# Relay_Switch.net
KiCad netlist of a schematic drawn in EAGLE
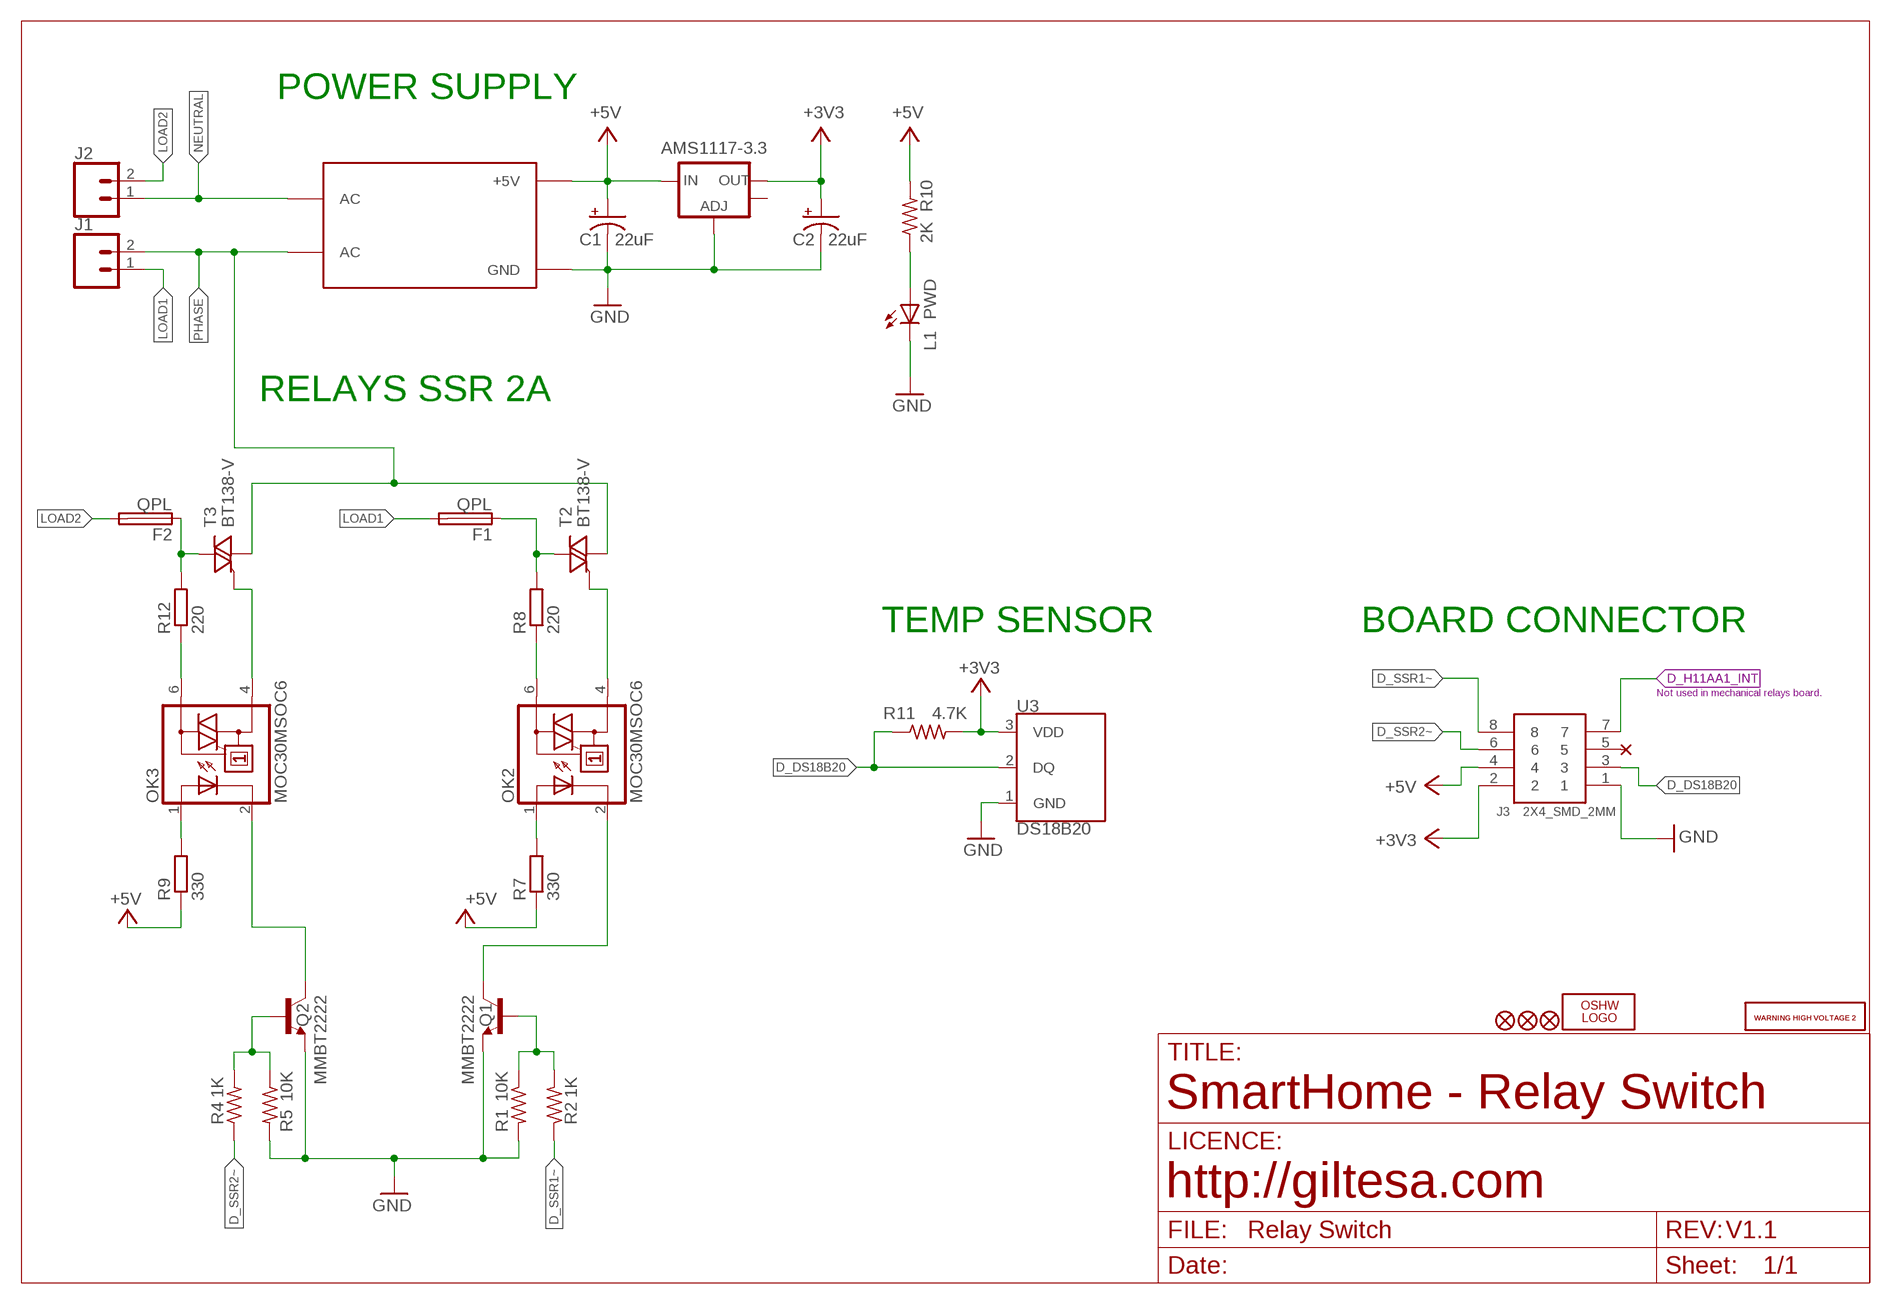
[diagram p0: schematic, sheet 1]

(export (version "E")
  (design (tool "Eeschema 10.0.6"))
  (components
    (comp (ref "AMS1117-3.3")
      (value "V_REG_LM1117SOT223")
      (footprint "eagle-import:SOT223")
      (libsource (lib "eagle-import") (part "V_REG_LM1117SOT223"))
    )
    (comp (ref "C1")
      (value "22uF")
      (footprint "eagle-import:EIA3528")
      (libsource (lib "eagle-import") (part "CAP_POL3528"))
    )
    (comp (ref "C2")
      (value "22uF")
      (footprint "eagle-import:EIA3528")
      (libsource (lib "eagle-import") (part "CAP_POL3528"))
    )
    (comp (ref "F1")
      (value "QPL")
      (footprint "eagle-import:TE5")
      (libsource (lib "eagle-import") (part "TE5"))
    )
    (comp (ref "F2")
      (value "QPL")
      (footprint "eagle-import:TE5")
      (libsource (lib "eagle-import") (part "TE5"))
    )
    (comp (ref "J1")
      (value "TERMINAL_5MM_2P")
      (footprint "eagle-import:TERMINAL_5MM_2P")
      (libsource (lib "eagle-import") (part "TERMINAL_5MM_2P"))
    )
    (comp (ref "J2")
      (value "TERMINAL_5MM_2P")
      (footprint "eagle-import:TERMINAL_5MM_2P")
      (libsource (lib "eagle-import") (part "TERMINAL_5MM_2P"))
    )
    (comp (ref "J3")
      (value "2X4_SMD_2MM")
      (footprint "eagle-import:2X4_SMD_2.0MM")
      (libsource (lib "eagle-import") (part "2X4_SMD_2.0MM"))
    )
    (comp (ref "L1")
      (value "PWD")
      (footprint "eagle-import:CHIP-LED0805")
      (libsource (lib "eagle-import") (part "LEDCHIP-LED0805"))
    )
    (comp (ref "LOGO1")
      (value "OSHW_LOGO_FILLX0150-NT")
      (footprint "eagle-import:OSHW_FILLX150_NOTEXT")
      (libsource (lib "eagle-import") (part "OSHW_LOGO_FILLX0150-NT"))
    )
    (comp (ref "OK2")
      (value "MOC30MSOC6")
      (footprint "eagle-import:DIL6-SMD")
      (libsource (lib "eagle-import") (part "MOC30MSOC6"))
    )
    (comp (ref "OK3")
      (value "MOC30MSOC6")
      (footprint "eagle-import:DIL6-SMD")
      (libsource (lib "eagle-import") (part "MOC30MSOC6"))
    )
    (comp (ref "Q1")
      (value "MMBT2222")
      (footprint "eagle-import:SOT23")
      (libsource (lib "eagle-import") (part "TRANSISTOR_NPNSOT23"))
    )
    (comp (ref "Q2")
      (value "MMBT2222")
      (footprint "eagle-import:SOT23")
      (libsource (lib "eagle-import") (part "TRANSISTOR_NPNSOT23"))
    )
    (comp (ref "R1")
      (value "10K")
      (footprint "eagle-import:R0603")
      (libsource (lib "eagle-import") (part "R0603"))
    )
    (comp (ref "R2")
      (value "1K")
      (footprint "eagle-import:R0603")
      (libsource (lib "eagle-import") (part "R0603"))
    )
    (comp (ref "R4")
      (value "1K")
      (footprint "eagle-import:R0603")
      (libsource (lib "eagle-import") (part "R0603"))
    )
    (comp (ref "R5")
      (value "10K")
      (footprint "eagle-import:R0603")
      (libsource (lib "eagle-import") (part "R0603"))
    )
    (comp (ref "R7")
      (value "330")
      (footprint "eagle-import:M0805")
      (libsource (lib "eagle-import") (part "R-EU_M0805"))
    )
    (comp (ref "R8")
      (value "220")
      (footprint "eagle-import:M0805")
      (libsource (lib "eagle-import") (part "R-EU_M0805"))
    )
    (comp (ref "R9")
      (value "330")
      (footprint "eagle-import:M0805")
      (libsource (lib "eagle-import") (part "R-EU_M0805"))
    )
    (comp (ref "R10")
      (value "2K")
      (footprint "eagle-import:R0603")
      (libsource (lib "eagle-import") (part "R0603"))
    )
    (comp (ref "R11")
      (value "4.7K")
      (footprint "eagle-import:R0603")
      (libsource (lib "eagle-import") (part "R0603"))
    )
    (comp (ref "R12")
      (value "220")
      (footprint "eagle-import:M0805")
      (libsource (lib "eagle-import") (part "R-EU_M0805"))
    )
    (comp (ref "T2")
      (value "BT138-V")
      (footprint "eagle-import:TO220BV")
      (libsource (lib "eagle-import") (part "BT138-V"))
    )
    (comp (ref "T3")
      (value "BT138-V")
      (footprint "eagle-import:TO220BV")
      (libsource (lib "eagle-import") (part "BT138-V"))
    )
    (comp (ref "U$1")
      (value "HILINK_HLK-PM01_5V")
      (footprint "eagle-import:HILINK_HLK-PM01_5V")
      (libsource (lib "eagle-import") (part "HILINK_HLK-PM01_5V"))
    )
    (comp (ref "U$3")
      (value "WARNING_HIGH_VOLTAGE_2")
      (footprint "eagle-import:WARNING_HIGH_VOLTAGE_2")
      (libsource (lib "eagle-import") (part "WARNING_HIGH_VOLTAGE_2"))
    )
    (comp (ref "U$4")
      (value "WARNING_HIGH_VOLTAGE_2")
      (footprint "eagle-import:WARNING_HIGH_VOLTAGE_2")
      (libsource (lib "eagle-import") (part "WARNING_HIGH_VOLTAGE_2"))
    )
    (comp (ref "U$6")
      (value "FIDUCIAL1X2")
      (footprint "eagle-import:FIDUCIAL-1X2")
      (libsource (lib "eagle-import") (part "FIDUCIAL1X2"))
    )
    (comp (ref "U$7")
      (value "FIDUCIAL1X2")
      (footprint "eagle-import:FIDUCIAL-1X2")
      (libsource (lib "eagle-import") (part "FIDUCIAL1X2"))
    )
    (comp (ref "U$14")
      (value "FIDUCIAL1X2")
      (footprint "eagle-import:FIDUCIAL-1X2")
      (libsource (lib "eagle-import") (part "FIDUCIAL1X2"))
    )
    (comp (ref "U3")
      (value "DS18B20")
      (footprint "eagle-import:DS18B20")
      (libsource (lib "eagle-import") (part "DS18B20"))
    )
  )
  (nets
    (net (code "1") (name "+3V3") (class "Default")
      (node (ref "AMS1117-3.3") (pin "2") (pinfunction "OUT_2") (pintype "output"))
      (node (ref "C2") (pin "A") (pinfunction "+_A") (pintype "passive"))
      (node (ref "J3") (pin "2") (pinfunction "2_2") (pintype "bidirectional"))
      (node (ref "R11") (pin "2") (pinfunction "2_2") (pintype "passive"))
      (node (ref "U3") (pin "3") (pinfunction "VDD_3") (pintype "power_in"))
    )
    (net (code "2") (name "+5V") (class "Default")
      (node (ref "AMS1117-3.3") (pin "3") (pinfunction "IN_3") (pintype "input"))
      (node (ref "C1") (pin "A") (pinfunction "+_A") (pintype "passive"))
      (node (ref "J3") (pin "4") (pinfunction "4_4") (pintype "bidirectional"))
      (node (ref "R10") (pin "2") (pinfunction "2_2") (pintype "passive"))
      (node (ref "R7") (pin "1") (pinfunction "1_1") (pintype "passive"))
      (node (ref "R9") (pin "1") (pinfunction "1_1") (pintype "passive"))
      (node (ref "U$1") (pin "+5V") (pinfunction "+5V_+5V") (pintype "output"))
    )
    (net (code "3") (name "/D_SSR1~{}") (class "Default")
      (node (ref "J3") (pin "8") (pinfunction "8_8") (pintype "bidirectional"))
      (node (ref "R2") (pin "1") (pinfunction "1_1") (pintype "passive"))
    )
    (net (code "4") (name "/D_SSR2~{}") (class "Default")
      (node (ref "J3") (pin "6") (pinfunction "6_6") (pintype "bidirectional"))
      (node (ref "R4") (pin "1") (pinfunction "1_1") (pintype "passive"))
    )
    (net (code "5") (name "D_DS18B20") (class "Default")
      (node (ref "J3") (pin "3") (pinfunction "3_3") (pintype "bidirectional"))
      (node (ref "R11") (pin "1") (pinfunction "1_1") (pintype "passive"))
      (node (ref "U3") (pin "2") (pinfunction "DQ_2") (pintype "bidirectional"))
    )
    (net (code "6") (name "D_H11AA1_INT") (class "Default")
      (node (ref "J3") (pin "7") (pinfunction "7_7") (pintype "bidirectional"))
    )
    (net (code "7") (name "GND") (class "Default")
      (node (ref "AMS1117-3.3") (pin "1") (pinfunction "ADJ_1") (pintype "input"))
      (node (ref "C1") (pin "C") (pinfunction "-_C") (pintype "passive"))
      (node (ref "C2") (pin "C") (pinfunction "-_C") (pintype "passive"))
      (node (ref "J3") (pin "1") (pinfunction "1_1") (pintype "bidirectional"))
      (node (ref "L1") (pin "C") (pinfunction "C_C") (pintype "passive"))
      (node (ref "Q1") (pin "2") (pinfunction "E_2") (pintype "passive"))
      (node (ref "Q2") (pin "2") (pinfunction "E_2") (pintype "passive"))
      (node (ref "R1") (pin "2") (pinfunction "2_2") (pintype "passive"))
      (node (ref "R5") (pin "2") (pinfunction "2_2") (pintype "passive"))
      (node (ref "U$1") (pin "GND") (pinfunction "GND_GND") (pintype "output"))
      (node (ref "U3") (pin "1") (pinfunction "GND_1") (pintype "power_in"))
    )
    (net (code "8") (name "LOAD1") (class "Default")
      (node (ref "F1") (pin "2") (pinfunction "2_2") (pintype "passive"))
      (node (ref "J1") (pin "1") (pinfunction "1_1") (pintype "passive"))
    )
    (net (code "9") (name "LOAD2") (class "Default")
      (node (ref "F2") (pin "2") (pinfunction "2_2") (pintype "passive"))
      (node (ref "J2") (pin "2") (pinfunction "2_2") (pintype "passive"))
    )
    (net (code "10") (name "NEUTRAL") (class "Default")
      (node (ref "J2") (pin "1") (pinfunction "1_1") (pintype "passive"))
      (node (ref "U$1") (pin "AC@2") (pinfunction "AC_AC@2") (pintype "input"))
    )
    (net (code "11") (name "Net-(L1-PadA)") (class "Default")
      (node (ref "L1") (pin "A") (pinfunction "A_A") (pintype "passive"))
      (node (ref "R10") (pin "1") (pinfunction "1_1") (pintype "passive"))
    )
    (net (code "12") (name "Net-(OK2-A)") (class "Default")
      (node (ref "OK2") (pin "1") (pinfunction "A_1") (pintype "passive"))
      (node (ref "R7") (pin "2") (pinfunction "2_2") (pintype "passive"))
    )
    (net (code "13") (name "Net-(OK2-A1)") (class "Default")
      (node (ref "OK2") (pin "4") (pinfunction "A1_4") (pintype "passive"))
      (node (ref "T2") (pin "G") (pinfunction "G_G") (pintype "passive"))
    )
    (net (code "14") (name "Net-(OK2-A2)") (class "Default")
      (node (ref "OK2") (pin "6") (pinfunction "A2_6") (pintype "passive"))
      (node (ref "R8") (pin "1") (pinfunction "1_1") (pintype "passive"))
    )
    (net (code "15") (name "Net-(OK2-C)") (class "Default")
      (node (ref "OK2") (pin "2") (pinfunction "C_2") (pintype "passive"))
      (node (ref "Q1") (pin "3") (pinfunction "C_3") (pintype "passive"))
    )
    (net (code "16") (name "Net-(OK3-A)") (class "Default")
      (node (ref "OK3") (pin "1") (pinfunction "A_1") (pintype "passive"))
      (node (ref "R9") (pin "2") (pinfunction "2_2") (pintype "passive"))
    )
    (net (code "17") (name "Net-(OK3-A1)") (class "Default")
      (node (ref "OK3") (pin "4") (pinfunction "A1_4") (pintype "passive"))
      (node (ref "T3") (pin "G") (pinfunction "G_G") (pintype "passive"))
    )
    (net (code "18") (name "Net-(OK3-A2)") (class "Default")
      (node (ref "OK3") (pin "6") (pinfunction "A2_6") (pintype "passive"))
      (node (ref "R12") (pin "1") (pinfunction "1_1") (pintype "passive"))
    )
    (net (code "19") (name "Net-(OK3-C)") (class "Default")
      (node (ref "OK3") (pin "2") (pinfunction "C_2") (pintype "passive"))
      (node (ref "Q2") (pin "3") (pinfunction "C_3") (pintype "passive"))
    )
    (net (code "20") (name "Net-(Q1-B)") (class "Default")
      (node (ref "Q1") (pin "1") (pinfunction "B_1") (pintype "passive"))
      (node (ref "R1") (pin "1") (pinfunction "1_1") (pintype "passive"))
      (node (ref "R2") (pin "2") (pinfunction "2_2") (pintype "passive"))
    )
    (net (code "21") (name "Net-(Q2-B)") (class "Default")
      (node (ref "Q2") (pin "1") (pinfunction "B_1") (pintype "passive"))
      (node (ref "R4") (pin "2") (pinfunction "2_2") (pintype "passive"))
      (node (ref "R5") (pin "1") (pinfunction "1_1") (pintype "passive"))
    )
    (net (code "22") (name "Net-(T2-A2)") (class "Default")
      (node (ref "F1") (pin "1") (pinfunction "1_1") (pintype "passive"))
      (node (ref "R8") (pin "2") (pinfunction "2_2") (pintype "passive"))
      (node (ref "T2") (pin "T2") (pinfunction "A2_T2") (pintype "passive"))
    )
    (net (code "23") (name "Net-(T3-A2)") (class "Default")
      (node (ref "F2") (pin "1") (pinfunction "1_1") (pintype "passive"))
      (node (ref "R12") (pin "2") (pinfunction "2_2") (pintype "passive"))
      (node (ref "T3") (pin "T2") (pinfunction "A2_T2") (pintype "passive"))
    )
    (net (code "24") (name "PHASE") (class "Default")
      (node (ref "J1") (pin "2") (pinfunction "2_2") (pintype "passive"))
      (node (ref "T2") (pin "T1") (pinfunction "A1_T1") (pintype "passive"))
      (node (ref "T3") (pin "T1") (pinfunction "A1_T1") (pintype "passive"))
      (node (ref "U$1") (pin "AC@1") (pinfunction "AC_AC@1") (pintype "input"))
    )
    (net (code "25") (name "unconnected-(AMS1117-3.3-OUT-Pad4)") (class "Default")
      (node (ref "AMS1117-3.3") (pin "4") (pinfunction "OUT_4") (pintype "output"))
    )
    (net (code "26") (name "unconnected-(J3-Pad5)") (class "Default")
      (node (ref "J3") (pin "5") (pinfunction "5_5") (pintype "bidirectional"))
    )
  )
)
